# BusDup.net
KiCad netlist of a schematic drawn in Altium Designer
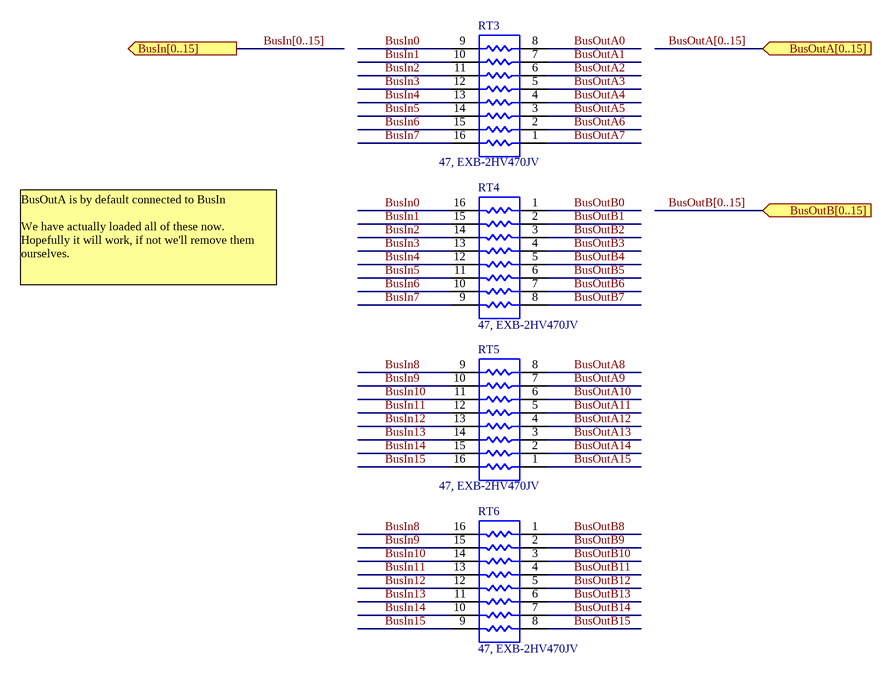
[diagram p0: BusDup.SchDoc]

(export (version "E")
  (design (tool "Eeschema 10.0.6"))
  (components
    (comp (ref "RT3")
      (value "47, EXB-2HV470JV")
      (footprint "0402_Array_2HV")
      (description "RES ARRAY 47 OHM SMD")
      (fields (field (name "MANUFACTURER") "Panasonic - ECG"))
      (libsource (lib "MGMEZZ04") (part "Res_Pack"))
    )
    (comp (ref "RT4")
      (value "47, EXB-2HV470JV")
      (footprint "0402_Array_2HV")
      (description "RES ARRAY 47 OHM SMD")
      (fields (field (name "MANUFACTURER") "Panasonic - ECG"))
      (libsource (lib "MGMEZZ04") (part "Res_Pack"))
    )
    (comp (ref "RT5")
      (value "47, EXB-2HV470JV")
      (footprint "0402_Array_2HV")
      (description "RES ARRAY 47 OHM SMD")
      (fields (field (name "MANUFACTURER") "Panasonic - ECG"))
      (libsource (lib "MGMEZZ04") (part "Res_Pack"))
    )
    (comp (ref "RT6")
      (value "47, EXB-2HV470JV")
      (footprint "0402_Array_2HV")
      (description "RES ARRAY 47 OHM SMD")
      (fields (field (name "MANUFACTURER") "Panasonic - ECG"))
      (libsource (lib "MGMEZZ04") (part "Res_Pack"))
    )
  )
  (nets
    (net (code "1") (name "/BusIn0") (class "Default")
      (node (ref "RT3") (pin "9") (pinfunction "9_9") (pintype "passive"))
      (node (ref "RT4") (pin "16") (pinfunction "16_16") (pintype "passive"))
    )
    (net (code "2") (name "/BusIn1") (class "Default")
      (node (ref "RT3") (pin "10") (pinfunction "10_10") (pintype "passive"))
      (node (ref "RT4") (pin "15") (pinfunction "15_15") (pintype "passive"))
    )
    (net (code "3") (name "/BusIn2") (class "Default")
      (node (ref "RT3") (pin "11") (pinfunction "11_11") (pintype "passive"))
      (node (ref "RT4") (pin "14") (pinfunction "14_14") (pintype "passive"))
    )
    (net (code "4") (name "/BusIn3") (class "Default")
      (node (ref "RT3") (pin "12") (pinfunction "12_12") (pintype "passive"))
      (node (ref "RT4") (pin "13") (pinfunction "13_13") (pintype "passive"))
    )
    (net (code "5") (name "/BusIn4") (class "Default")
      (node (ref "RT3") (pin "13") (pinfunction "13_13") (pintype "passive"))
      (node (ref "RT4") (pin "12") (pinfunction "12_12") (pintype "passive"))
    )
    (net (code "6") (name "/BusIn5") (class "Default")
      (node (ref "RT3") (pin "14") (pinfunction "14_14") (pintype "passive"))
      (node (ref "RT4") (pin "11") (pinfunction "11_11") (pintype "passive"))
    )
    (net (code "7") (name "/BusIn6") (class "Default")
      (node (ref "RT3") (pin "15") (pinfunction "15_15") (pintype "passive"))
      (node (ref "RT4") (pin "10") (pinfunction "10_10") (pintype "passive"))
    )
    (net (code "8") (name "/BusIn7") (class "Default")
      (node (ref "RT3") (pin "16") (pinfunction "16_16") (pintype "passive"))
      (node (ref "RT4") (pin "9") (pinfunction "9_9") (pintype "passive"))
    )
    (net (code "9") (name "/BusIn8") (class "Default")
      (node (ref "RT5") (pin "9") (pinfunction "9_9") (pintype "passive"))
      (node (ref "RT6") (pin "16") (pinfunction "16_16") (pintype "passive"))
    )
    (net (code "10") (name "/BusIn9") (class "Default")
      (node (ref "RT5") (pin "10") (pinfunction "10_10") (pintype "passive"))
      (node (ref "RT6") (pin "15") (pinfunction "15_15") (pintype "passive"))
    )
    (net (code "11") (name "/BusIn10") (class "Default")
      (node (ref "RT5") (pin "11") (pinfunction "11_11") (pintype "passive"))
      (node (ref "RT6") (pin "14") (pinfunction "14_14") (pintype "passive"))
    )
    (net (code "12") (name "/BusIn11") (class "Default")
      (node (ref "RT5") (pin "12") (pinfunction "12_12") (pintype "passive"))
      (node (ref "RT6") (pin "13") (pinfunction "13_13") (pintype "passive"))
    )
    (net (code "13") (name "/BusIn12") (class "Default")
      (node (ref "RT5") (pin "13") (pinfunction "13_13") (pintype "passive"))
      (node (ref "RT6") (pin "12") (pinfunction "12_12") (pintype "passive"))
    )
    (net (code "14") (name "/BusIn13") (class "Default")
      (node (ref "RT5") (pin "14") (pinfunction "14_14") (pintype "passive"))
      (node (ref "RT6") (pin "11") (pinfunction "11_11") (pintype "passive"))
    )
    (net (code "15") (name "/BusIn14") (class "Default")
      (node (ref "RT5") (pin "15") (pinfunction "15_15") (pintype "passive"))
      (node (ref "RT6") (pin "10") (pinfunction "10_10") (pintype "passive"))
    )
    (net (code "16") (name "/BusIn15") (class "Default")
      (node (ref "RT5") (pin "16") (pinfunction "16_16") (pintype "passive"))
      (node (ref "RT6") (pin "9") (pinfunction "9_9") (pintype "passive"))
    )
    (net (code "18") (name "/BusOutA0") (class "Default")
      (node (ref "RT3") (pin "8") (pinfunction "8_8") (pintype "passive"))
    )
    (net (code "19") (name "/BusOutA1") (class "Default")
      (node (ref "RT3") (pin "7") (pinfunction "7_7") (pintype "passive"))
    )
    (net (code "20") (name "/BusOutA2") (class "Default")
      (node (ref "RT3") (pin "6") (pinfunction "6_6") (pintype "passive"))
    )
    (net (code "21") (name "/BusOutA3") (class "Default")
      (node (ref "RT3") (pin "5") (pinfunction "5_5") (pintype "passive"))
    )
    (net (code "22") (name "/BusOutA4") (class "Default")
      (node (ref "RT3") (pin "4") (pinfunction "4_4") (pintype "passive"))
    )
    (net (code "23") (name "/BusOutA5") (class "Default")
      (node (ref "RT3") (pin "3") (pinfunction "3_3") (pintype "passive"))
    )
    (net (code "24") (name "/BusOutA6") (class "Default")
      (node (ref "RT3") (pin "2") (pinfunction "2_2") (pintype "passive"))
    )
    (net (code "25") (name "/BusOutA7") (class "Default")
      (node (ref "RT3") (pin "1") (pinfunction "1_1") (pintype "passive"))
    )
    (net (code "26") (name "/BusOutA8") (class "Default")
      (node (ref "RT5") (pin "8") (pinfunction "8_8") (pintype "passive"))
    )
    (net (code "27") (name "/BusOutA9") (class "Default")
      (node (ref "RT5") (pin "7") (pinfunction "7_7") (pintype "passive"))
    )
    (net (code "28") (name "/BusOutA10") (class "Default")
      (node (ref "RT5") (pin "6") (pinfunction "6_6") (pintype "passive"))
    )
    (net (code "29") (name "/BusOutA11") (class "Default")
      (node (ref "RT5") (pin "5") (pinfunction "5_5") (pintype "passive"))
    )
    (net (code "30") (name "/BusOutA12") (class "Default")
      (node (ref "RT5") (pin "4") (pinfunction "4_4") (pintype "passive"))
    )
    (net (code "31") (name "/BusOutA13") (class "Default")
      (node (ref "RT5") (pin "3") (pinfunction "3_3") (pintype "passive"))
    )
    (net (code "32") (name "/BusOutA14") (class "Default")
      (node (ref "RT5") (pin "2") (pinfunction "2_2") (pintype "passive"))
    )
    (net (code "33") (name "/BusOutA15") (class "Default")
      (node (ref "RT5") (pin "1") (pinfunction "1_1") (pintype "passive"))
    )
    (net (code "35") (name "/BusOutB0") (class "Default")
      (node (ref "RT4") (pin "1") (pinfunction "1_1") (pintype "passive"))
    )
    (net (code "36") (name "/BusOutB1") (class "Default")
      (node (ref "RT4") (pin "2") (pinfunction "2_2") (pintype "passive"))
    )
    (net (code "37") (name "/BusOutB2") (class "Default")
      (node (ref "RT4") (pin "3") (pinfunction "3_3") (pintype "passive"))
    )
    (net (code "38") (name "/BusOutB3") (class "Default")
      (node (ref "RT4") (pin "4") (pinfunction "4_4") (pintype "passive"))
    )
    (net (code "39") (name "/BusOutB4") (class "Default")
      (node (ref "RT4") (pin "5") (pinfunction "5_5") (pintype "passive"))
    )
    (net (code "40") (name "/BusOutB5") (class "Default")
      (node (ref "RT4") (pin "6") (pinfunction "6_6") (pintype "passive"))
    )
    (net (code "41") (name "/BusOutB6") (class "Default")
      (node (ref "RT4") (pin "7") (pinfunction "7_7") (pintype "passive"))
    )
    (net (code "42") (name "/BusOutB7") (class "Default")
      (node (ref "RT4") (pin "8") (pinfunction "8_8") (pintype "passive"))
    )
    (net (code "43") (name "/BusOutB8") (class "Default")
      (node (ref "RT6") (pin "1") (pinfunction "1_1") (pintype "passive"))
    )
    (net (code "44") (name "/BusOutB9") (class "Default")
      (node (ref "RT6") (pin "2") (pinfunction "2_2") (pintype "passive"))
    )
    (net (code "45") (name "/BusOutB10") (class "Default")
      (node (ref "RT6") (pin "3") (pinfunction "3_3") (pintype "passive"))
    )
    (net (code "46") (name "/BusOutB11") (class "Default")
      (node (ref "RT6") (pin "4") (pinfunction "4_4") (pintype "passive"))
    )
    (net (code "47") (name "/BusOutB12") (class "Default")
      (node (ref "RT6") (pin "5") (pinfunction "5_5") (pintype "passive"))
    )
    (net (code "48") (name "/BusOutB13") (class "Default")
      (node (ref "RT6") (pin "6") (pinfunction "6_6") (pintype "passive"))
    )
    (net (code "49") (name "/BusOutB14") (class "Default")
      (node (ref "RT6") (pin "7") (pinfunction "7_7") (pintype "passive"))
    )
    (net (code "50") (name "/BusOutB15") (class "Default")
      (node (ref "RT6") (pin "8") (pinfunction "8_8") (pintype "passive"))
    )
  )
)
